# remote.net
KiCad netlist of a schematic drawn in EAGLE
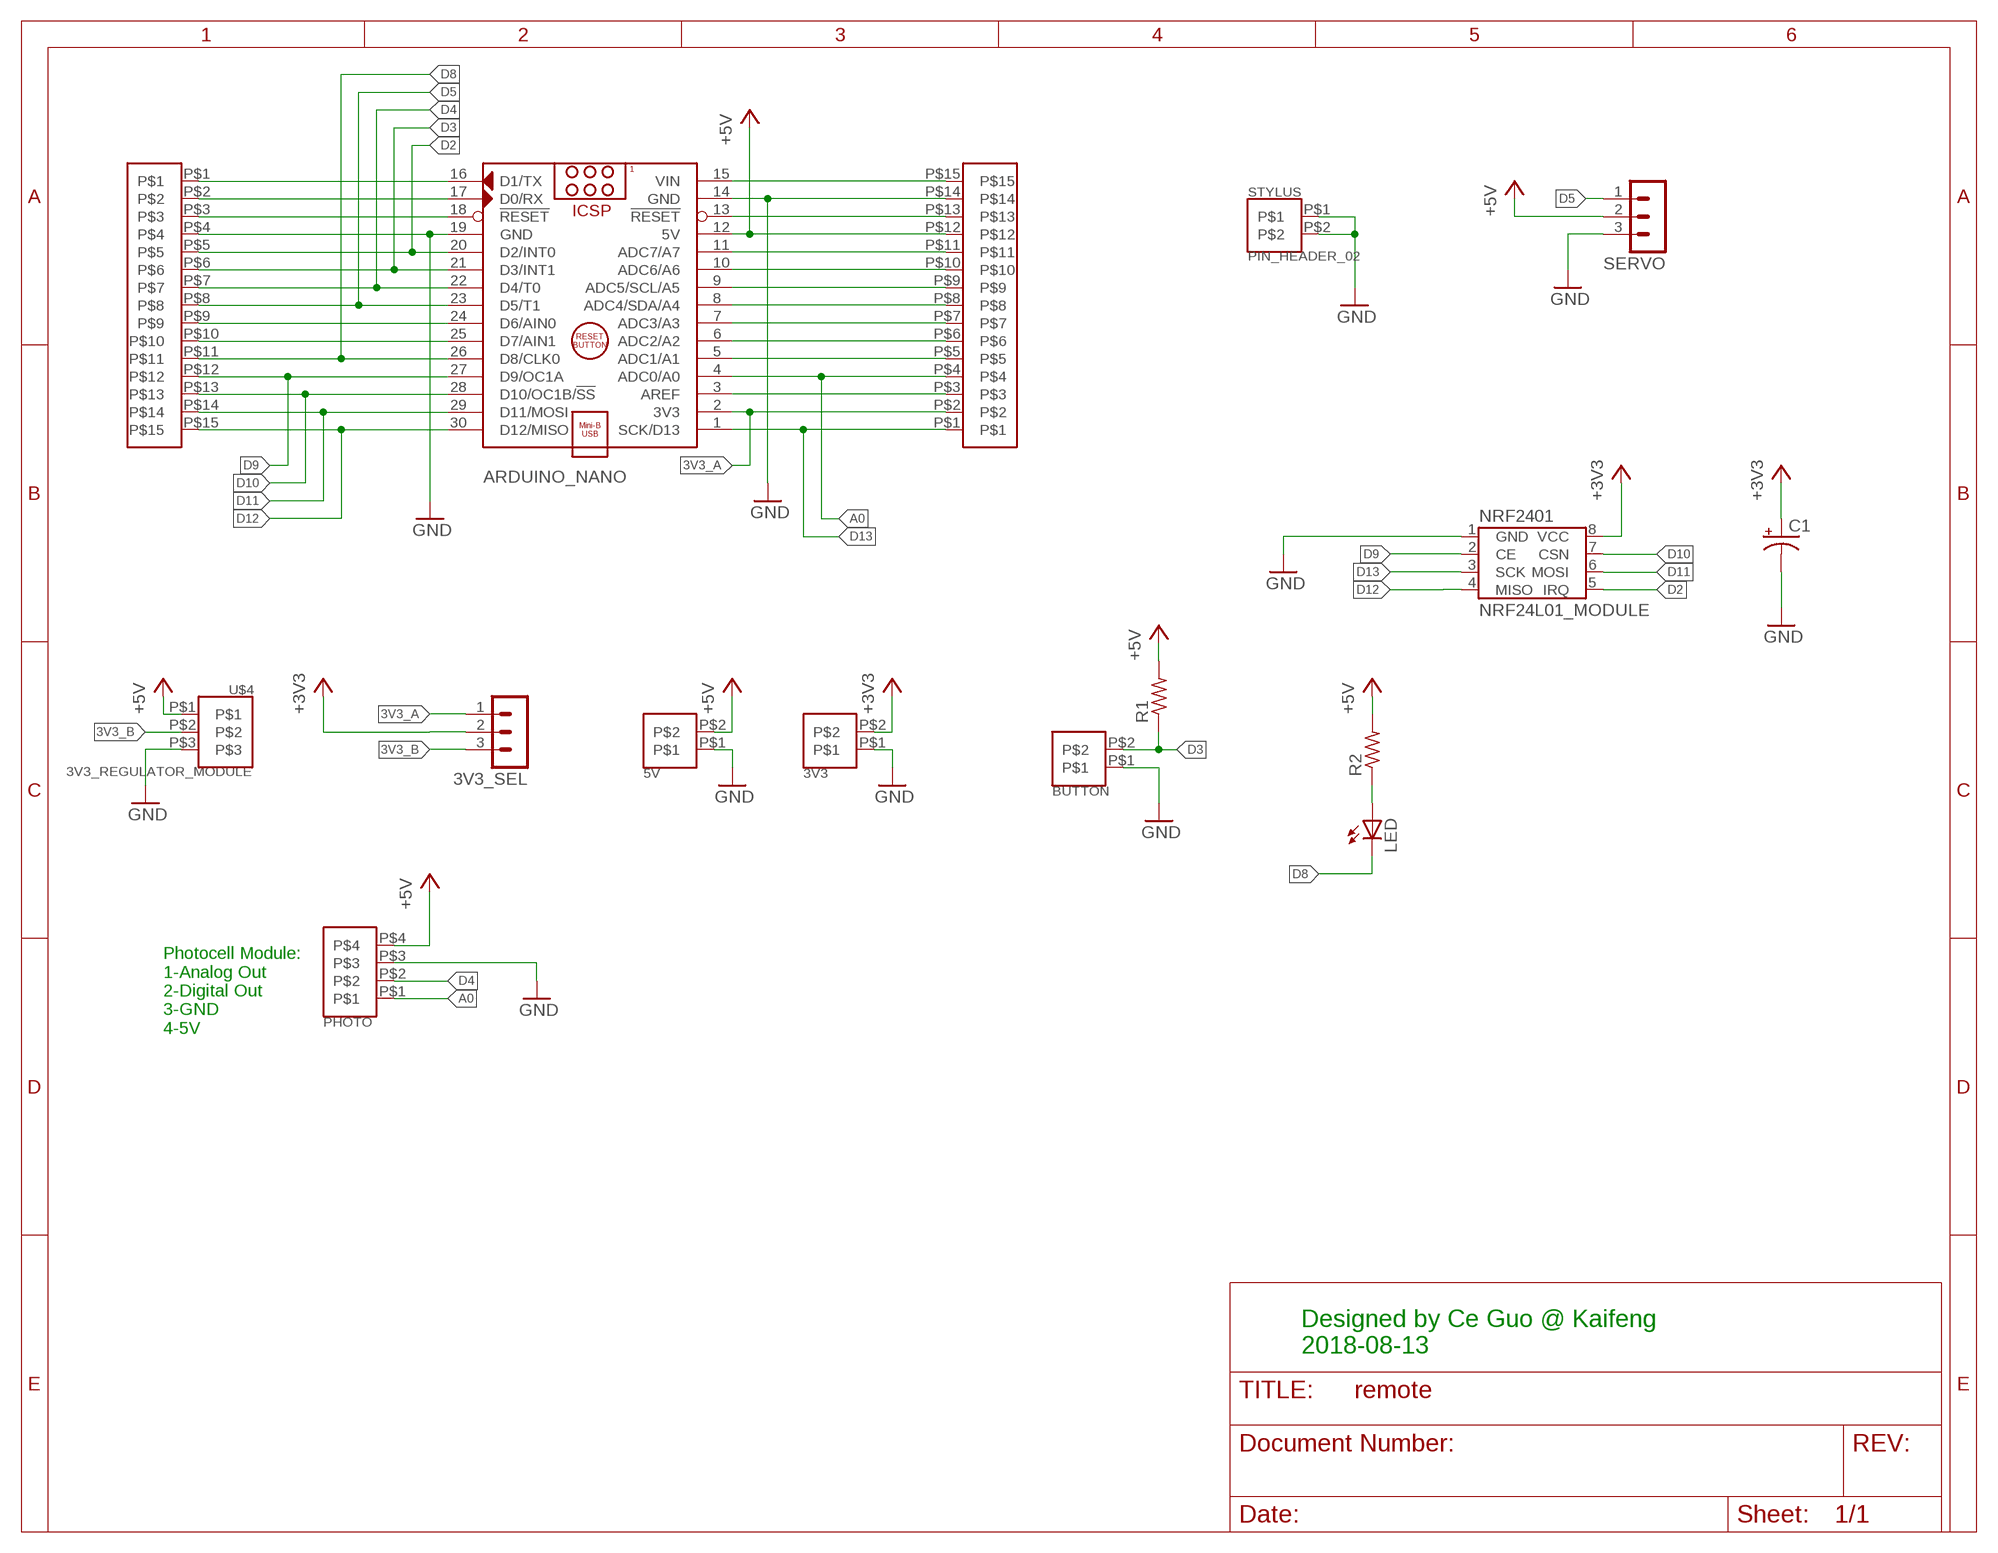
[diagram p0: schematic, sheet 1]

(export (version "E")
  (design (tool "Eeschema 10.0.6"))
  (components
    (comp (ref "3V3")
      (value "PIN_HEADER_02")
      (footprint "eagle-import:PIN_HEADER_02")
      (libsource (lib "eagle-import") (part "PIN_HEADER_02"))
    )
    (comp (ref "3V3_SEL")
      (value "MA03-1")
      (footprint "eagle-import:MA03-1")
      (libsource (lib "eagle-import") (part "MA03-1"))
    )
    (comp (ref "5V")
      (value "PIN_HEADER_02")
      (footprint "eagle-import:PIN_HEADER_02")
      (libsource (lib "eagle-import") (part "PIN_HEADER_02"))
    )
    (comp (ref "ARDUINO_NANO")
      (value "ARDUINO_NANO_NO_HOLE")
      (footprint "eagle-import:ARDUINO_NANO_B")
      (libsource (lib "eagle-import") (part "ARDUINO_NANO_NO_HOLE"))
    )
    (comp (ref "BUTTON")
      (value "PIN_HEADER_02")
      (footprint "eagle-import:PIN_HEADER_02")
      (libsource (lib "eagle-import") (part "PIN_HEADER_02"))
    )
    (comp (ref "C1")
      (value "CPOL-USE5-5")
      (footprint "eagle-import:E5-5")
      (libsource (lib "eagle-import") (part "CPOL-USE5-5"))
    )
    (comp (ref "LED")
      (value "LED_HEADER")
      (footprint "eagle-import:PIN_HEADER_02")
      (libsource (lib "eagle-import") (part "LED_HEADER"))
    )
    (comp (ref "NRF2401")
      (value "NRF24L01_MODULE")
      (footprint "eagle-import:NRF24_MODULE")
      (libsource (lib "eagle-import") (part "NRF24L01_MODULE"))
    )
    (comp (ref "PHOTO")
      (value "PIN_HEADER_04")
      (footprint "eagle-import:PIN_HEADER_04")
      (libsource (lib "eagle-import") (part "PIN_HEADER_04"))
    )
    (comp (ref "R1")
      (value "R-US_R0805")
      (footprint "eagle-import:R0805")
      (libsource (lib "eagle-import") (part "R-US_R0805"))
    )
    (comp (ref "R2")
      (value "R-US_R0805")
      (footprint "eagle-import:R0805")
      (libsource (lib "eagle-import") (part "R-US_R0805"))
    )
    (comp (ref "SERVO")
      (value "MA03-1")
      (footprint "eagle-import:MA03-1")
      (libsource (lib "eagle-import") (part "MA03-1"))
    )
    (comp (ref "STYLUS")
      (value "PIN_HEADER_02")
      (footprint "eagle-import:PIN_HEADER_02")
      (libsource (lib "eagle-import") (part "PIN_HEADER_02"))
    )
    (comp (ref "U$2")
      (value "PIN_HEADER_15")
      (footprint "eagle-import:PIN_HEADER_15")
      (libsource (lib "eagle-import") (part "PIN_HEADER_15"))
    )
    (comp (ref "U$3")
      (value "PIN_HEADER_15")
      (footprint "eagle-import:PIN_HEADER_15")
      (libsource (lib "eagle-import") (part "PIN_HEADER_15"))
    )
    (comp (ref "U$4")
      (value "3V3_REGULATOR_MODULE")
      (footprint "eagle-import:3V3_REGULATOR_MODULE")
      (libsource (lib "eagle-import") (part "3V3_REGULATOR_MODULE"))
    )
  )
  (nets
    (net (code "1") (name "+3V3") (class "Default")
      (node (ref "3V3") (pin "P$2") (pinfunction "P$2_P$2") (pintype "bidirectional"))
      (node (ref "3V3_SEL") (pin "2") (pinfunction "2_2") (pintype "passive"))
      (node (ref "C1") (pin "+") (pinfunction "+_+") (pintype "passive"))
      (node (ref "NRF2401") (pin "8") (pinfunction "VCC_8") (pintype "bidirectional"))
    )
    (net (code "2") (name "+5V") (class "Default")
      (node (ref "5V") (pin "P$2") (pinfunction "P$2_P$2") (pintype "bidirectional"))
      (node (ref "ARDUINO_NANO") (pin "12") (pinfunction "5V_12") (pintype "power_in"))
      (node (ref "PHOTO") (pin "P$4") (pinfunction "P$4_P$4") (pintype "bidirectional"))
      (node (ref "R1") (pin "2") (pinfunction "2_2") (pintype "passive"))
      (node (ref "R2") (pin "2") (pinfunction "2_2") (pintype "passive"))
      (node (ref "SERVO") (pin "2") (pinfunction "2_2") (pintype "passive"))
      (node (ref "U$3") (pin "P$12") (pinfunction "P$12_P$12") (pintype "bidirectional"))
      (node (ref "U$4") (pin "P$1") (pinfunction "P$1_P$1") (pintype "bidirectional"))
    )
    (net (code "3") (name "3V3_A") (class "Default")
      (node (ref "3V3_SEL") (pin "1") (pinfunction "1_1") (pintype "passive"))
      (node (ref "ARDUINO_NANO") (pin "2") (pinfunction "3V3_2") (pintype "output"))
      (node (ref "U$3") (pin "P$2") (pinfunction "P$2_P$2") (pintype "bidirectional"))
    )
    (net (code "4") (name "3V3_B") (class "Default")
      (node (ref "3V3_SEL") (pin "3") (pinfunction "3_3") (pintype "passive"))
      (node (ref "U$4") (pin "P$2") (pinfunction "P$2_P$2") (pintype "bidirectional"))
    )
    (net (code "5") (name "A0") (class "Default")
      (node (ref "ARDUINO_NANO") (pin "4") (pinfunction "ADC0/A0_4") (pintype "bidirectional"))
      (node (ref "PHOTO") (pin "P$1") (pinfunction "P$1_P$1") (pintype "bidirectional"))
      (node (ref "U$3") (pin "P$4") (pinfunction "P$4_P$4") (pintype "bidirectional"))
    )
    (net (code "6") (name "D2") (class "Default")
      (node (ref "ARDUINO_NANO") (pin "20") (pinfunction "D2/INT0_20") (pintype "bidirectional"))
      (node (ref "NRF2401") (pin "5") (pinfunction "IRQ_5") (pintype "bidirectional"))
      (node (ref "U$2") (pin "P$5") (pinfunction "P$5_P$5") (pintype "bidirectional"))
    )
    (net (code "7") (name "D3") (class "Default")
      (node (ref "ARDUINO_NANO") (pin "21") (pinfunction "D3/INT1_21") (pintype "bidirectional"))
      (node (ref "BUTTON") (pin "P$2") (pinfunction "P$2_P$2") (pintype "bidirectional"))
      (node (ref "R1") (pin "1") (pinfunction "1_1") (pintype "passive"))
      (node (ref "U$2") (pin "P$6") (pinfunction "P$6_P$6") (pintype "bidirectional"))
    )
    (net (code "8") (name "D4") (class "Default")
      (node (ref "ARDUINO_NANO") (pin "22") (pinfunction "D4/T0_22") (pintype "bidirectional"))
      (node (ref "PHOTO") (pin "P$2") (pinfunction "P$2_P$2") (pintype "bidirectional"))
      (node (ref "U$2") (pin "P$7") (pinfunction "P$7_P$7") (pintype "bidirectional"))
    )
    (net (code "9") (name "D5") (class "Default")
      (node (ref "ARDUINO_NANO") (pin "23") (pinfunction "D5/T1_23") (pintype "bidirectional"))
      (node (ref "SERVO") (pin "1") (pinfunction "1_1") (pintype "passive"))
      (node (ref "U$2") (pin "P$8") (pinfunction "P$8_P$8") (pintype "bidirectional"))
    )
    (net (code "10") (name "D8") (class "Default")
      (node (ref "ARDUINO_NANO") (pin "26") (pinfunction "D8/CLK0_26") (pintype "bidirectional"))
      (node (ref "LED") (pin "P$2") (pinfunction "C_P$2") (pintype "passive"))
      (node (ref "U$2") (pin "P$11") (pinfunction "P$11_P$11") (pintype "bidirectional"))
    )
    (net (code "11") (name "D9") (class "Default")
      (node (ref "ARDUINO_NANO") (pin "27") (pinfunction "D9/OC1A_27") (pintype "bidirectional"))
      (node (ref "NRF2401") (pin "2") (pinfunction "CE_2") (pintype "bidirectional"))
      (node (ref "U$2") (pin "P$12") (pinfunction "P$12_P$12") (pintype "bidirectional"))
    )
    (net (code "12") (name "D10") (class "Default")
      (node (ref "ARDUINO_NANO") (pin "28") (pinfunction "D10/OC1B/~{SS}_28") (pintype "bidirectional"))
      (node (ref "NRF2401") (pin "7") (pinfunction "CSN_7") (pintype "bidirectional"))
      (node (ref "U$2") (pin "P$13") (pinfunction "P$13_P$13") (pintype "bidirectional"))
    )
    (net (code "13") (name "D11") (class "Default")
      (node (ref "ARDUINO_NANO") (pin "29") (pinfunction "D11/MOSI_29") (pintype "bidirectional"))
      (node (ref "NRF2401") (pin "6") (pinfunction "MOSI_6") (pintype "bidirectional"))
      (node (ref "U$2") (pin "P$14") (pinfunction "P$14_P$14") (pintype "bidirectional"))
    )
    (net (code "14") (name "D12") (class "Default")
      (node (ref "ARDUINO_NANO") (pin "30") (pinfunction "D12/MISO_30") (pintype "bidirectional"))
      (node (ref "NRF2401") (pin "4") (pinfunction "MISO_4") (pintype "bidirectional"))
      (node (ref "U$2") (pin "P$15") (pinfunction "P$15_P$15") (pintype "bidirectional"))
    )
    (net (code "15") (name "D13") (class "Default")
      (node (ref "ARDUINO_NANO") (pin "1") (pinfunction "SCK/D13_1") (pintype "bidirectional"))
      (node (ref "NRF2401") (pin "3") (pinfunction "SCK_3") (pintype "bidirectional"))
      (node (ref "U$3") (pin "P$1") (pinfunction "P$1_P$1") (pintype "bidirectional"))
    )
    (net (code "16") (name "GND") (class "Default")
      (node (ref "3V3") (pin "P$1") (pinfunction "P$1_P$1") (pintype "bidirectional"))
      (node (ref "5V") (pin "P$1") (pinfunction "P$1_P$1") (pintype "bidirectional"))
      (node (ref "ARDUINO_NANO") (pin "14") (pinfunction "GND_14") (pintype "power_in"))
      (node (ref "ARDUINO_NANO") (pin "19") (pinfunction "GND_19") (pintype "power_in"))
      (node (ref "BUTTON") (pin "P$1") (pinfunction "P$1_P$1") (pintype "bidirectional"))
      (node (ref "C1") (pin "-") (pinfunction "-_-") (pintype "passive"))
      (node (ref "NRF2401") (pin "1") (pinfunction "GND_1") (pintype "bidirectional"))
      (node (ref "PHOTO") (pin "P$3") (pinfunction "P$3_P$3") (pintype "bidirectional"))
      (node (ref "SERVO") (pin "3") (pinfunction "3_3") (pintype "passive"))
      (node (ref "STYLUS") (pin "P$1") (pinfunction "P$1_P$1") (pintype "bidirectional"))
      (node (ref "STYLUS") (pin "P$2") (pinfunction "P$2_P$2") (pintype "bidirectional"))
      (node (ref "U$2") (pin "P$4") (pinfunction "P$4_P$4") (pintype "bidirectional"))
      (node (ref "U$3") (pin "P$14") (pinfunction "P$14_P$14") (pintype "bidirectional"))
      (node (ref "U$4") (pin "P$3") (pinfunction "P$3_P$3") (pintype "bidirectional"))
    )
    (net (code "17") (name "Net-(ARDUINO_NANO-ADC1{slash}A1)") (class "Default")
      (node (ref "ARDUINO_NANO") (pin "5") (pinfunction "ADC1/A1_5") (pintype "bidirectional"))
      (node (ref "U$3") (pin "P$5") (pinfunction "P$5_P$5") (pintype "bidirectional"))
    )
    (net (code "18") (name "Net-(ARDUINO_NANO-ADC2{slash}A2)") (class "Default")
      (node (ref "ARDUINO_NANO") (pin "6") (pinfunction "ADC2/A2_6") (pintype "bidirectional"))
      (node (ref "U$3") (pin "P$6") (pinfunction "P$6_P$6") (pintype "bidirectional"))
    )
    (net (code "19") (name "Net-(ARDUINO_NANO-ADC3{slash}A3)") (class "Default")
      (node (ref "ARDUINO_NANO") (pin "7") (pinfunction "ADC3/A3_7") (pintype "bidirectional"))
      (node (ref "U$3") (pin "P$7") (pinfunction "P$7_P$7") (pintype "bidirectional"))
    )
    (net (code "20") (name "Net-(ARDUINO_NANO-ADC4{slash}SDA{slash}A4)") (class "Default")
      (node (ref "ARDUINO_NANO") (pin "8") (pinfunction "ADC4/SDA/A4_8") (pintype "bidirectional"))
      (node (ref "U$3") (pin "P$8") (pinfunction "P$8_P$8") (pintype "bidirectional"))
    )
    (net (code "21") (name "Net-(ARDUINO_NANO-ADC5{slash}SCL{slash}A5)") (class "Default")
      (node (ref "ARDUINO_NANO") (pin "9") (pinfunction "ADC5/SCL/A5_9") (pintype "bidirectional"))
      (node (ref "U$3") (pin "P$9") (pinfunction "P$9_P$9") (pintype "bidirectional"))
    )
    (net (code "22") (name "Net-(ARDUINO_NANO-ADC6{slash}A6)") (class "Default")
      (node (ref "ARDUINO_NANO") (pin "10") (pinfunction "ADC6/A6_10") (pintype "bidirectional"))
      (node (ref "U$3") (pin "P$10") (pinfunction "P$10_P$10") (pintype "bidirectional"))
    )
    (net (code "23") (name "Net-(ARDUINO_NANO-ADC7{slash}A7)") (class "Default")
      (node (ref "ARDUINO_NANO") (pin "11") (pinfunction "ADC7/A7_11") (pintype "bidirectional"))
      (node (ref "U$3") (pin "P$11") (pinfunction "P$11_P$11") (pintype "bidirectional"))
    )
    (net (code "24") (name "Net-(ARDUINO_NANO-AREF)") (class "Default")
      (node (ref "ARDUINO_NANO") (pin "3") (pinfunction "AREF_3") (pintype "input"))
      (node (ref "U$3") (pin "P$3") (pinfunction "P$3_P$3") (pintype "bidirectional"))
    )
    (net (code "25") (name "Net-(ARDUINO_NANO-D0{slash}RX)") (class "Default")
      (node (ref "ARDUINO_NANO") (pin "17") (pinfunction "D0/RX_17") (pintype "bidirectional"))
      (node (ref "U$2") (pin "P$2") (pinfunction "P$2_P$2") (pintype "bidirectional"))
    )
    (net (code "26") (name "Net-(ARDUINO_NANO-D1{slash}TX)") (class "Default")
      (node (ref "ARDUINO_NANO") (pin "16") (pinfunction "D1/TX_16") (pintype "bidirectional"))
      (node (ref "U$2") (pin "P$1") (pinfunction "P$1_P$1") (pintype "bidirectional"))
    )
    (net (code "27") (name "Net-(ARDUINO_NANO-D6{slash}AIN0)") (class "Default")
      (node (ref "ARDUINO_NANO") (pin "24") (pinfunction "D6/AIN0_24") (pintype "bidirectional"))
      (node (ref "U$2") (pin "P$9") (pinfunction "P$9_P$9") (pintype "bidirectional"))
    )
    (net (code "28") (name "Net-(ARDUINO_NANO-D7{slash}AIN1)") (class "Default")
      (node (ref "ARDUINO_NANO") (pin "25") (pinfunction "D7/AIN1_25") (pintype "bidirectional"))
      (node (ref "U$2") (pin "P$10") (pinfunction "P$10_P$10") (pintype "bidirectional"))
    )
    (net (code "29") (name "Net-(ARDUINO_NANO-VIN)") (class "Default")
      (node (ref "ARDUINO_NANO") (pin "15") (pinfunction "VIN_15") (pintype "power_in"))
      (node (ref "U$3") (pin "P$15") (pinfunction "P$15_P$15") (pintype "bidirectional"))
    )
    (net (code "30") (name "Net-(ARDUINO_NANO-~{RESET}-Pad13)") (class "Default")
      (node (ref "ARDUINO_NANO") (pin "13") (pinfunction "~{RESET}_13") (pintype "input"))
      (node (ref "U$3") (pin "P$13") (pinfunction "P$13_P$13") (pintype "bidirectional"))
    )
    (net (code "31") (name "Net-(ARDUINO_NANO-~{RESET}-Pad18)") (class "Default")
      (node (ref "ARDUINO_NANO") (pin "18") (pinfunction "~{RESET}_18") (pintype "input"))
      (node (ref "U$2") (pin "P$3") (pinfunction "P$3_P$3") (pintype "bidirectional"))
    )
    (net (code "32") (name "Net-(LED-A)") (class "Default")
      (node (ref "LED") (pin "P$1") (pinfunction "A_P$1") (pintype "passive"))
      (node (ref "R2") (pin "1") (pinfunction "1_1") (pintype "passive"))
    )
  )
)
